# Addon-mapleCUx_HM-RFM69-RFM95-V12-001.net
KiCad netlist of a schematic drawn in EAGLE
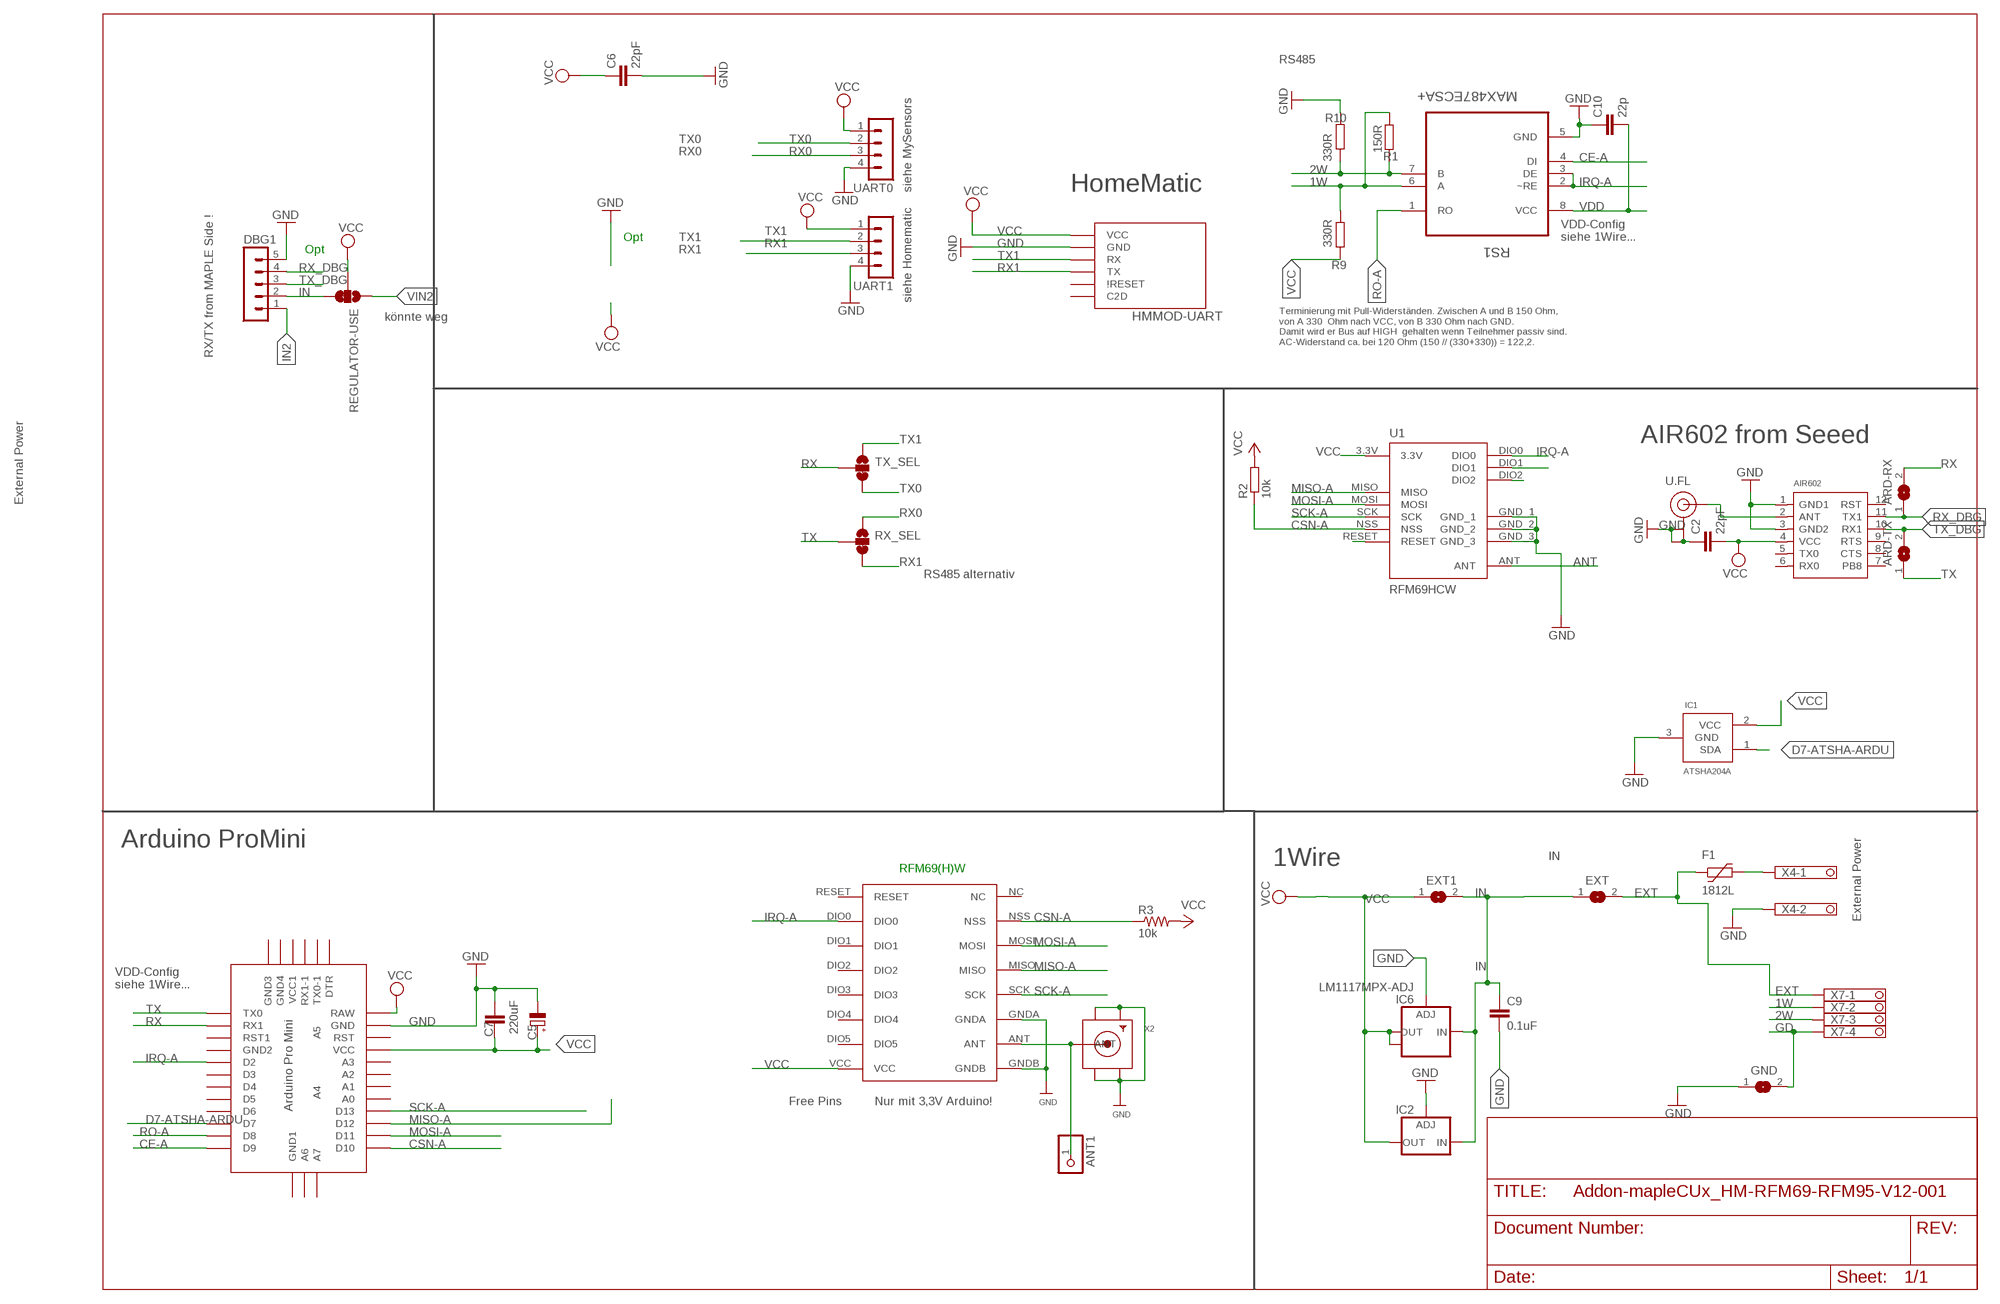
[diagram p0: schematic, sheet 1]

(export (version "E")
  (design (tool "Eeschema 10.0.6"))
  (components
    (comp (ref "AIR602")
      (value "AIR602")
      (footprint "eagle-import:MODULE12P-2.0-10X12MM")
      (libsource (lib "eagle-import") (part "AIR602"))
    )
    (comp (ref "ANT1")
      (value "PINHD-1X1")
      (footprint "eagle-import:1X01")
      (libsource (lib "eagle-import") (part "PINHD-1X1"))
    )
    (comp (ref "ARD-RX")
      (value "SJ")
      (footprint "eagle-import:SJ")
      (libsource (lib "eagle-import") (part "SJ"))
    )
    (comp (ref "ARD-TX")
      (value "SJ")
      (footprint "eagle-import:SJ")
      (libsource (lib "eagle-import") (part "SJ"))
    )
    (comp (ref "C2")
      (value "22pF")
      (footprint "eagle-import:C0805")
      (libsource (lib "eagle-import") (part "C-EUC0805"))
    )
    (comp (ref "C5")
      (value "220uF")
      (footprint "eagle-import:E5-8,5")
      (libsource (lib "eagle-import") (part "CPOL-EUE5-8.5"))
    )
    (comp (ref "C6")
      (value "22pF")
      (footprint "eagle-import:C0805")
      (libsource (lib "eagle-import") (part "C-EUC0805"))
    )
    (comp (ref "C7")
      (value "C-EUC1812")
      (footprint "eagle-import:C1812")
      (libsource (lib "eagle-import") (part "C-EUC1812"))
    )
    (comp (ref "C9")
      (value "0.1uF")
      (footprint "eagle-import:C1206")
      (libsource (lib "eagle-import") (part "C-EUC1206"))
    )
    (comp (ref "C10")
      (value "22p")
      (footprint "eagle-import:C0805")
      (libsource (lib "eagle-import") (part "C-EUC0805"))
    )
    (comp (ref "DBG1")
      (value "MA05-1")
      (footprint "eagle-import:MA05-1")
      (libsource (lib "eagle-import") (part "MA05-1"))
    )
    (comp (ref "EXT") (value "SJ") (footprint "eagle-import:SJ") (libsource (lib "eagle-import") (part "SJ")))
    (comp (ref "EXT1")
      (value "SJ")
      (footprint "eagle-import:SJ")
      (libsource (lib "eagle-import") (part "SJ"))
    )
    (comp (ref "F1")
      (value "1812L")
      (footprint "eagle-import:1812L")
      (libsource (lib "eagle-import") (part "1812L"))
    )
    (comp (ref "GND") (value "SJ") (footprint "eagle-import:SJ") (libsource (lib "eagle-import") (part "SJ")))
    (comp (ref "HMMOD-UART")
      (value "HM-MOD-UARTDIL")
      (footprint "eagle-import:HM-MOD-UART-DIL")
      (libsource (lib "eagle-import") (part "HM-MOD-UARTDIL"))
    )
    (comp (ref "IC1")
      (value "ATSHA204A")
      (footprint "eagle-import:SOT23")
      (libsource (lib "eagle-import") (part "ATSHA204A"))
    )
    (comp (ref "IC2")
      (value "LD117ADT50TR")
      (footprint "eagle-import:DPACK")
      (libsource (lib "eagle-import") (part "LD117A?DT50TR"))
    )
    (comp (ref "IC6")
      (value "LM1117MPX-ADJ")
      (footprint "eagle-import:SOT223")
      (libsource (lib "eagle-import") (part "LM1117MPX-ADJ"))
    )
    (comp (ref "R1")
      (value "150R")
      (footprint "eagle-import:R0805")
      (libsource (lib "eagle-import") (part "R-EU_R0805"))
    )
    (comp (ref "R2")
      (value "10k")
      (footprint "eagle-import:M0805")
      (libsource (lib "eagle-import") (part "R-EU_M0805"))
    )
    (comp (ref "R3")
      (value "10k")
      (footprint "eagle-import:0805")
      (libsource (lib "eagle-import") (part "RESISTOR0805-RES"))
    )
    (comp (ref "R9")
      (value "330R")
      (footprint "eagle-import:R0805")
      (libsource (lib "eagle-import") (part "R-EU_R0805"))
    )
    (comp (ref "R10")
      (value "330R")
      (footprint "eagle-import:R0805")
      (libsource (lib "eagle-import") (part "R-EU_R0805"))
    )
    (comp (ref "REGULATOR-USE")
      (value "JUMPER-SMT_3_1-NC_TRACE_SILK")
      (footprint "eagle-import:SMT-JUMPER_3_1-NC_TRACE_SILK")
      (libsource (lib "eagle-import") (part "JUMPER-SMT_3_1-NC_TRACE_SILK"))
    )
    (comp (ref "RFM69W")
      (value "RFM69HW")
      (footprint "eagle-import:RFM")
      (libsource (lib "eagle-import") (part "RFM69HW"))
    )
    (comp (ref "RS1")
      (value "MAX487ECSA+")
      (footprint "eagle-import:SOIC127P600X175-8N")
      (libsource (lib "eagle-import") (part "MAX487ECSA+"))
    )
    (comp (ref "RX_SEL")
      (value "JUMPER-SMT_3_1-NC_TRACE_SILK")
      (footprint "eagle-import:SMT-JUMPER_3_1-NC_TRACE_SILK")
      (libsource (lib "eagle-import") (part "JUMPER-SMT_3_1-NC_TRACE_SILK"))
    )
    (comp (ref "TX_SEL")
      (value "JUMPER-SMT_3_1-NC_TRACE_SILK")
      (footprint "eagle-import:SMT-JUMPER_3_1-NC_TRACE_SILK")
      (libsource (lib "eagle-import") (part "JUMPER-SMT_3_1-NC_TRACE_SILK"))
    )
    (comp (ref "U$2")
      (value "ABK-PRO-MINI")
      (footprint "eagle-import:ABK-PRO-MINI")
      (libsource (lib "eagle-import") (part "ABK-PRO-MINI"))
    )
    (comp (ref "U.FL")
      (value "U.FL")
      (footprint "eagle-import:U.FL")
      (libsource (lib "eagle-import") (part "U.FL"))
    )
    (comp (ref "U1")
      (value "RFM69HCW")
      (footprint "eagle-import:RFM69HCW-XXXS2")
      (libsource (lib "eagle-import") (part "RFM69HCW"))
    )
    (comp (ref "UART0")
      (value "MA04-1")
      (footprint "eagle-import:MA04-1")
      (libsource (lib "eagle-import") (part "MA04-1"))
    )
    (comp (ref "UART1")
      (value "MA04-1")
      (footprint "eagle-import:MA04-1")
      (libsource (lib "eagle-import") (part "MA04-1"))
    )
    (comp (ref "X2")
      (value "SMACONNECTOR_EDGE")
      (footprint "eagle-import:SMA_EDGELAUNCH")
      (libsource (lib "eagle-import") (part "SMACONNECTOR_EDGE"))
    )
    (comp (ref "X4")
      (value "1751248")
      (footprint "eagle-import:1751248")
      (libsource (lib "eagle-import") (part "1751248"))
    )
    (comp (ref "X7")
      (value "1751264")
      (footprint "eagle-import:1751264")
      (libsource (lib "eagle-import") (part "1751264"))
    )
  )
  (nets
    (net (code "1") (name "/1W") (class "Default")
      (node (ref "R1") (pin "1") (pinfunction "1_1") (pintype "passive"))
      (node (ref "R9") (pin "2") (pinfunction "2_2") (pintype "passive"))
      (node (ref "RS1") (pin "6") (pinfunction "A_6") (pintype "bidirectional"))
      (node (ref "X7") (pin "2") (pinfunction "K_2") (pintype "passive"))
    )
    (net (code "2") (name "/2W") (class "Default")
      (node (ref "R1") (pin "2") (pinfunction "2_2") (pintype "passive"))
      (node (ref "R10") (pin "1") (pinfunction "1_1") (pintype "passive"))
      (node (ref "RS1") (pin "7") (pinfunction "B_7") (pintype "bidirectional"))
      (node (ref "X7") (pin "3") (pinfunction "K_3") (pintype "passive"))
    )
    (net (code "3") (name "/ANT") (class "Default")
      (node (ref "ANT1") (pin "1") (pinfunction "1_1") (pintype "passive"))
      (node (ref "RFM69W") (pin "ANT") (pinfunction "ANT_ANT") (pintype "bidirectional"))
      (node (ref "U1") (pin "ANT") (pinfunction "ANT_ANT") (pintype "passive"))
      (node (ref "X2") (pin "P") (pinfunction "ANT_P") (pintype "bidirectional"))
    )
    (net (code "4") (name "/CE-A") (class "Default")
      (node (ref "RS1") (pin "4") (pinfunction "DI_4") (pintype "input"))
      (node (ref "U$2") (pin "D9") (pinfunction "D9_D9") (pintype "bidirectional"))
    )
    (net (code "5") (name "/CSN-A") (class "Default")
      (node (ref "R2") (pin "1") (pinfunction "1_1") (pintype "passive"))
      (node (ref "R3") (pin "1") (pinfunction "1_1") (pintype "passive"))
      (node (ref "RFM69W") (pin "NSS") (pinfunction "NSS_NSS") (pintype "bidirectional"))
      (node (ref "U$2") (pin "D10") (pinfunction "D10_D10") (pintype "bidirectional"))
      (node (ref "U1") (pin "NSS") (pinfunction "NSS_NSS") (pintype "input"))
    )
    (net (code "6") (name "/EXT") (class "Default")
      (node (ref "EXT") (pin "2") (pinfunction "2_2") (pintype "passive"))
      (node (ref "F1") (pin "P$1") (pinfunction "1_P$1") (pintype "passive"))
      (node (ref "X7") (pin "1") (pinfunction "K_1") (pintype "passive"))
    )
    (net (code "7") (name "/GD") (class "Default")
      (node (ref "GND") (pin "2") (pinfunction "2_2") (pintype "passive"))
      (node (ref "X7") (pin "4") (pinfunction "K_4") (pintype "passive"))
    )
    (net (code "8") (name "/IN") (class "Default")
      (node (ref "C9") (pin "1") (pinfunction "1_1") (pintype "passive"))
      (node (ref "DBG1") (pin "2") (pinfunction "2_2") (pintype "passive"))
      (node (ref "EXT") (pin "1") (pinfunction "1_1") (pintype "passive"))
      (node (ref "EXT1") (pin "2") (pinfunction "2_2") (pintype "passive"))
      (node (ref "IC2") (pin "3") (pinfunction "IN_3") (pintype "input"))
      (node (ref "IC6") (pin "3") (pinfunction "IN_3") (pintype "input"))
      (node (ref "REGULATOR-USE") (pin "3") (pinfunction "3_3") (pintype "passive"))
    )
    (net (code "9") (name "/IRQ-A") (class "Default")
      (node (ref "RFM69W") (pin "DIO0") (pinfunction "DIO0_DIO0") (pintype "bidirectional"))
      (node (ref "RS1") (pin "2") (pinfunction "~{RE}_2") (pintype "input"))
      (node (ref "RS1") (pin "3") (pinfunction "DE_3") (pintype "input"))
      (node (ref "U$2") (pin "D2") (pinfunction "D2_D2") (pintype "bidirectional"))
      (node (ref "U1") (pin "DIO0") (pinfunction "DIO0_DIO0") (pintype "bidirectional"))
    )
    (net (code "10") (name "/MISO-A") (class "Default")
      (node (ref "RFM69W") (pin "MISO") (pinfunction "MISO_MISO") (pintype "bidirectional"))
      (node (ref "U$2") (pin "D12") (pinfunction "D12_D12") (pintype "bidirectional"))
      (node (ref "U1") (pin "MISO") (pinfunction "MISO_MISO") (pintype "bidirectional"))
    )
    (net (code "11") (name "/MOSI-A") (class "Default")
      (node (ref "RFM69W") (pin "MOSI") (pinfunction "MOSI_MOSI") (pintype "bidirectional"))
      (node (ref "U$2") (pin "D11") (pinfunction "D11_D11") (pintype "bidirectional"))
      (node (ref "U1") (pin "MOSI") (pinfunction "MOSI_MOSI") (pintype "input"))
    )
    (net (code "12") (name "/RX") (class "Default")
      (node (ref "ARD-RX") (pin "2") (pinfunction "2_2") (pintype "passive"))
      (node (ref "TX_SEL") (pin "2") (pinfunction "2_2") (pintype "passive"))
      (node (ref "U$2") (pin "RX1") (pinfunction "RX1_RX1") (pintype "bidirectional"))
    )
    (net (code "13") (name "/RX0") (class "Default")
      (node (ref "RX_SEL") (pin "1") (pinfunction "1_1") (pintype "passive"))
      (node (ref "UART0") (pin "3") (pinfunction "3_3") (pintype "passive"))
    )
    (net (code "14") (name "/RX1") (class "Default")
      (node (ref "HMMOD-UART") (pin "5") (pinfunction "TX_5") (pintype "bidirectional"))
      (node (ref "RX_SEL") (pin "3") (pinfunction "3_3") (pintype "passive"))
      (node (ref "UART1") (pin "3") (pinfunction "3_3") (pintype "passive"))
    )
    (net (code "15") (name "/SCK-A") (class "Default")
      (node (ref "RFM69W") (pin "SCK") (pinfunction "SCK_SCK") (pintype "bidirectional"))
      (node (ref "U$2") (pin "D13") (pinfunction "D13_D13") (pintype "bidirectional"))
      (node (ref "U1") (pin "SCK") (pinfunction "SCK_SCK") (pintype "input"))
    )
    (net (code "16") (name "/TX") (class "Default")
      (node (ref "ARD-TX") (pin "1") (pinfunction "1_1") (pintype "passive"))
      (node (ref "RX_SEL") (pin "2") (pinfunction "2_2") (pintype "passive"))
      (node (ref "U$2") (pin "TX0") (pinfunction "TX0_TX0") (pintype "bidirectional"))
    )
    (net (code "17") (name "/TX0") (class "Default")
      (node (ref "TX_SEL") (pin "3") (pinfunction "3_3") (pintype "passive"))
      (node (ref "UART0") (pin "2") (pinfunction "2_2") (pintype "passive"))
    )
    (net (code "18") (name "/TX1") (class "Default")
      (node (ref "HMMOD-UART") (pin "6") (pinfunction "RX_6") (pintype "bidirectional"))
      (node (ref "TX_SEL") (pin "1") (pinfunction "1_1") (pintype "passive"))
      (node (ref "UART1") (pin "2") (pinfunction "2_2") (pintype "passive"))
    )
    (net (code "19") (name "/VDD") (class "Default")
      (node (ref "C10") (pin "2") (pinfunction "2_2") (pintype "passive"))
      (node (ref "RS1") (pin "8") (pinfunction "VCC_8") (pintype "power_in"))
    )
    (net (code "20") (name "D7-ATSHA-ARDU") (class "Default")
      (node (ref "IC1") (pin "1") (pinfunction "SDA_1") (pintype "bidirectional"))
      (node (ref "U$2") (pin "D7") (pinfunction "D7_D7") (pintype "bidirectional"))
    )
    (net (code "21") (name "GND") (class "Default")
      (node (ref "AIR602") (pin "1") (pinfunction "GND1_1") (pintype "bidirectional"))
      (node (ref "AIR602") (pin "3") (pinfunction "GND2_3") (pintype "bidirectional"))
      (node (ref "C10") (pin "1") (pinfunction "1_1") (pintype "passive"))
      (node (ref "C2") (pin "1") (pinfunction "1_1") (pintype "passive"))
      (node (ref "C5") (pin "-") (pinfunction "-_-") (pintype "passive"))
      (node (ref "C6") (pin "2") (pinfunction "2_2") (pintype "passive"))
      (node (ref "C7") (pin "1") (pinfunction "1_1") (pintype "passive"))
      (node (ref "C9") (pin "2") (pinfunction "2_2") (pintype "passive"))
      (node (ref "DBG1") (pin "5") (pinfunction "5_5") (pintype "passive"))
      (node (ref "GND") (pin "1") (pinfunction "1_1") (pintype "passive"))
      (node (ref "HMMOD-UART") (pin "2") (pinfunction "GND_2") (pintype "power_in"))
      (node (ref "IC1") (pin "3") (pinfunction "GND_3") (pintype "bidirectional"))
      (node (ref "IC2") (pin "1") (pinfunction "ADJ_1") (pintype "input"))
      (node (ref "IC6") (pin "1") (pinfunction "ADJ_1") (pintype "input"))
      (node (ref "R10") (pin "2") (pinfunction "2_2") (pintype "passive"))
      (node (ref "RFM69W") (pin "GNDA") (pinfunction "GNDA_GNDA") (pintype "bidirectional"))
      (node (ref "RFM69W") (pin "GNDB") (pinfunction "GNDB_GNDB") (pintype "bidirectional"))
      (node (ref "RS1") (pin "5") (pinfunction "GND_5") (pintype "passive"))
      (node (ref "U$2") (pin "GND") (pinfunction "GND_GND") (pintype "bidirectional"))
      (node (ref "U.FL") (pin "1") (pinfunction "GND_1") (pintype "bidirectional"))
      (node (ref "U.FL") (pin "2") (pinfunction "GND_2") (pintype "bidirectional"))
      (node (ref "U1") (pin "GND_1") (pinfunction "GND_1_GND_1") (pintype "power_in"))
      (node (ref "U1") (pin "GND_2") (pinfunction "GND_2_GND_2") (pintype "power_in"))
      (node (ref "U1") (pin "GND_3") (pinfunction "GND_3_GND_3") (pintype "power_in"))
      (node (ref "UART0") (pin "4") (pinfunction "4_4") (pintype "passive"))
      (node (ref "UART1") (pin "4") (pinfunction "4_4") (pintype "passive"))
      (node (ref "X2") (pin "GND@1") (pinfunction "GND4_GND@1") (pintype "power_in"))
      (node (ref "X2") (pin "GND@2") (pinfunction "GND3_GND@2") (pintype "power_in"))
      (node (ref "X2") (pin "GND@3") (pinfunction "GND2_GND@3") (pintype "power_in"))
      (node (ref "X2") (pin "GND@4") (pinfunction "GND1_GND@4") (pintype "power_in"))
      (node (ref "X4") (pin "2") (pinfunction "K_2") (pintype "passive"))
    )
    (net (code "22") (name "IN2") (class "Default")
      (node (ref "DBG1") (pin "1") (pinfunction "1_1") (pintype "passive"))
    )
    (net (code "23") (name "Net-(AIR602-ANT)") (class "Default")
      (node (ref "AIR602") (pin "2") (pinfunction "ANT_2") (pintype "bidirectional"))
      (node (ref "U.FL") (pin "FEED") (pinfunction "SIGNAL_FEED") (pintype "bidirectional"))
    )
    (net (code "24") (name "Net-(F1-2)") (class "Default")
      (node (ref "F1") (pin "P$2") (pinfunction "2_P$2") (pintype "passive"))
      (node (ref "X4") (pin "1") (pinfunction "K_1") (pintype "passive"))
    )
    (net (code "25") (name "RO-A") (class "Default")
      (node (ref "RS1") (pin "1") (pinfunction "RO_1") (pintype "output"))
      (node (ref "U$2") (pin "D8") (pinfunction "D8_D8") (pintype "bidirectional"))
    )
    (net (code "26") (name "RX_DBG") (class "Default")
      (node (ref "AIR602") (pin "11") (pinfunction "TX1_11") (pintype "bidirectional"))
      (node (ref "ARD-RX") (pin "1") (pinfunction "1_1") (pintype "passive"))
      (node (ref "DBG1") (pin "4") (pinfunction "4_4") (pintype "passive"))
    )
    (net (code "27") (name "TX_DBG") (class "Default")
      (node (ref "AIR602") (pin "10") (pinfunction "RX1_10") (pintype "bidirectional"))
      (node (ref "ARD-TX") (pin "2") (pinfunction "2_2") (pintype "passive"))
      (node (ref "DBG1") (pin "3") (pinfunction "3_3") (pintype "passive"))
    )
    (net (code "28") (name "VCC") (class "Default")
      (node (ref "AIR602") (pin "4") (pinfunction "VCC_4") (pintype "bidirectional"))
      (node (ref "C2") (pin "2") (pinfunction "2_2") (pintype "passive"))
      (node (ref "C5") (pin "+") (pinfunction "+_+") (pintype "passive"))
      (node (ref "C6") (pin "1") (pinfunction "1_1") (pintype "passive"))
      (node (ref "C7") (pin "2") (pinfunction "2_2") (pintype "passive"))
      (node (ref "EXT1") (pin "1") (pinfunction "1_1") (pintype "passive"))
      (node (ref "HMMOD-UART") (pin "1") (pinfunction "VCC_1") (pintype "power_in"))
      (node (ref "IC1") (pin "2") (pinfunction "VCC_2") (pintype "bidirectional"))
      (node (ref "IC2") (pin "4") (pinfunction "OUT_4") (pintype "passive"))
      (node (ref "IC6") (pin "2") (pinfunction "OUT_2") (pintype "passive"))
      (node (ref "IC6") (pin "TAB") (pinfunction "OUT1_TAB") (pintype "passive"))
      (node (ref "R2") (pin "2") (pinfunction "2_2") (pintype "passive"))
      (node (ref "R3") (pin "2") (pinfunction "2_2") (pintype "passive"))
      (node (ref "R9") (pin "1") (pinfunction "1_1") (pintype "passive"))
      (node (ref "REGULATOR-USE") (pin "2") (pinfunction "2_2") (pintype "passive"))
      (node (ref "RFM69W") (pin "VCC") (pinfunction "VCC_VCC") (pintype "bidirectional"))
      (node (ref "U$2") (pin "RAW") (pinfunction "RAW_RAW") (pintype "bidirectional"))
      (node (ref "U$2") (pin "VCC") (pinfunction "VCC_VCC") (pintype "bidirectional"))
      (node (ref "U1") (pin "3.3V") (pinfunction "3.3V_3.3V") (pintype "power_in"))
      (node (ref "UART0") (pin "1") (pinfunction "1_1") (pintype "passive"))
      (node (ref "UART1") (pin "1") (pinfunction "1_1") (pintype "passive"))
    )
    (net (code "29") (name "VIN2") (class "Default")
      (node (ref "REGULATOR-USE") (pin "1") (pinfunction "1_1") (pintype "passive"))
    )
    (net (code "30") (name "unconnected-(AIR602-CTS-Pad8)") (class "Default")
      (node (ref "AIR602") (pin "8") (pinfunction "CTS_8") (pintype "bidirectional"))
    )
    (net (code "31") (name "unconnected-(AIR602-PB8-Pad7)") (class "Default")
      (node (ref "AIR602") (pin "7") (pinfunction "PB8_7") (pintype "bidirectional"))
    )
    (net (code "32") (name "unconnected-(AIR602-RST-Pad12)") (class "Default")
      (node (ref "AIR602") (pin "12") (pinfunction "RST_12") (pintype "bidirectional"))
    )
    (net (code "33") (name "unconnected-(AIR602-RTS-Pad9)") (class "Default")
      (node (ref "AIR602") (pin "9") (pinfunction "RTS_9") (pintype "bidirectional"))
    )
    (net (code "34") (name "unconnected-(AIR602-RX0-Pad6)") (class "Default")
      (node (ref "AIR602") (pin "6") (pinfunction "RX0_6") (pintype "bidirectional"))
    )
    (net (code "35") (name "unconnected-(AIR602-TX0-Pad5)") (class "Default")
      (node (ref "AIR602") (pin "5") (pinfunction "TX0_5") (pintype "bidirectional"))
    )
    (net (code "36") (name "unconnected-(HMMOD-UART-C2D-Pad3)") (class "Default")
      (node (ref "HMMOD-UART") (pin "3") (pinfunction "C2D_3") (pintype "bidirectional"))
    )
    (net (code "37") (name "unconnected-(HMMOD-UART-\\~{RESET}-Pad4)") (class "Default")
      (node (ref "HMMOD-UART") (pin "4") (pinfunction "\\~{RESET}_4") (pintype "bidirectional"))
    )
    (net (code "38") (name "unconnected-(RFM69W-PadDIO1)") (class "Default")
      (node (ref "RFM69W") (pin "DIO1") (pinfunction "DIO1_DIO1") (pintype "bidirectional"))
    )
    (net (code "39") (name "unconnected-(RFM69W-PadDIO2)") (class "Default")
      (node (ref "RFM69W") (pin "DIO2") (pinfunction "DIO2_DIO2") (pintype "bidirectional"))
    )
    (net (code "40") (name "unconnected-(RFM69W-PadDIO3)") (class "Default")
      (node (ref "RFM69W") (pin "DIO3") (pinfunction "DIO3_DIO3") (pintype "bidirectional"))
    )
    (net (code "41") (name "unconnected-(RFM69W-PadDIO4)") (class "Default")
      (node (ref "RFM69W") (pin "DIO4") (pinfunction "DIO4_DIO4") (pintype "bidirectional"))
    )
    (net (code "42") (name "unconnected-(RFM69W-PadDIO5)") (class "Default")
      (node (ref "RFM69W") (pin "DIO5") (pinfunction "DIO5_DIO5") (pintype "bidirectional"))
    )
    (net (code "43") (name "unconnected-(RFM69W-PadNC)") (class "Default")
      (node (ref "RFM69W") (pin "NC") (pinfunction "NC_NC") (pintype "bidirectional"))
    )
    (net (code "44") (name "unconnected-(RFM69W-PadRESET)") (class "Default")
      (node (ref "RFM69W") (pin "RESET") (pinfunction "RESET_RESET") (pintype "bidirectional"))
    )
    (net (code "45") (name "unconnected-(U$2-GND1-PadGND4)") (class "Default")
      (node (ref "U$2") (pin "GND4") (pinfunction "GND1_GND4") (pintype "bidirectional"))
    )
    (net (code "46") (name "unconnected-(U$2-GND2-PadGND1)") (class "Default")
      (node (ref "U$2") (pin "GND1") (pinfunction "GND2_GND1") (pintype "bidirectional"))
    )
    (net (code "47") (name "unconnected-(U$2-GND3-PadGND2)") (class "Default")
      (node (ref "U$2") (pin "GND2") (pinfunction "GND3_GND2") (pintype "bidirectional"))
    )
    (net (code "48") (name "unconnected-(U$2-GND4-PadGND3)") (class "Default")
      (node (ref "U$2") (pin "GND3") (pinfunction "GND4_GND3") (pintype "bidirectional"))
    )
    (net (code "49") (name "unconnected-(U$2-PadA0)") (class "Default")
      (node (ref "U$2") (pin "A0") (pinfunction "A0_A0") (pintype "bidirectional"))
    )
    (net (code "50") (name "unconnected-(U$2-PadA1)") (class "Default")
      (node (ref "U$2") (pin "A1") (pinfunction "A1_A1") (pintype "bidirectional"))
    )
    (net (code "51") (name "unconnected-(U$2-PadA2)") (class "Default")
      (node (ref "U$2") (pin "A2") (pinfunction "A2_A2") (pintype "bidirectional"))
    )
    (net (code "52") (name "unconnected-(U$2-PadA3)") (class "Default")
      (node (ref "U$2") (pin "A3") (pinfunction "A3_A3") (pintype "bidirectional"))
    )
    (net (code "53") (name "unconnected-(U$2-PadA4)") (class "Default")
      (node (ref "U$2") (pin "A4") (pinfunction "A4_A4") (pintype "bidirectional"))
    )
    (net (code "54") (name "unconnected-(U$2-PadA5)") (class "Default")
      (node (ref "U$2") (pin "A5") (pinfunction "A5_A5") (pintype "bidirectional"))
    )
    (net (code "55") (name "unconnected-(U$2-PadA6)") (class "Default")
      (node (ref "U$2") (pin "A6") (pinfunction "A6_A6") (pintype "bidirectional"))
    )
    (net (code "56") (name "unconnected-(U$2-PadA7)") (class "Default")
      (node (ref "U$2") (pin "A7") (pinfunction "A7_A7") (pintype "bidirectional"))
    )
    (net (code "57") (name "unconnected-(U$2-PadD3)") (class "Default")
      (node (ref "U$2") (pin "D3") (pinfunction "D3_D3") (pintype "bidirectional"))
    )
    (net (code "58") (name "unconnected-(U$2-PadD4)") (class "Default")
      (node (ref "U$2") (pin "D4") (pinfunction "D4_D4") (pintype "bidirectional"))
    )
    (net (code "59") (name "unconnected-(U$2-PadD5)") (class "Default")
      (node (ref "U$2") (pin "D5") (pinfunction "D5_D5") (pintype "bidirectional"))
    )
    (net (code "60") (name "unconnected-(U$2-PadD6)") (class "Default")
      (node (ref "U$2") (pin "D6") (pinfunction "D6_D6") (pintype "bidirectional"))
    )
    (net (code "61") (name "unconnected-(U$2-PadDTR)") (class "Default")
      (node (ref "U$2") (pin "DTR") (pinfunction "DTR_DTR") (pintype "bidirectional"))
    )
    (net (code "62") (name "unconnected-(U$2-PadRST)") (class "Default")
      (node (ref "U$2") (pin "RST") (pinfunction "RST_RST") (pintype "bidirectional"))
    )
    (net (code "63") (name "unconnected-(U$2-PadRST1)") (class "Default")
      (node (ref "U$2") (pin "RST1") (pinfunction "RST1_RST1") (pintype "bidirectional"))
    )
    (net (code "64") (name "unconnected-(U$2-PadRX1-1)") (class "Default")
      (node (ref "U$2") (pin "RX1-1") (pinfunction "RX1-1_RX1-1") (pintype "bidirectional"))
    )
    (net (code "65") (name "unconnected-(U$2-PadTX0-1)") (class "Default")
      (node (ref "U$2") (pin "TX0-1") (pinfunction "TX0-1_TX0-1") (pintype "bidirectional"))
    )
    (net (code "66") (name "unconnected-(U$2-PadVCC1)") (class "Default")
      (node (ref "U$2") (pin "VCC1") (pinfunction "VCC1_VCC1") (pintype "bidirectional"))
    )
    (net (code "67") (name "unconnected-(U1-PadDIO1)") (class "Default")
      (node (ref "U1") (pin "DIO1") (pinfunction "DIO1_DIO1") (pintype "bidirectional"))
    )
    (net (code "68") (name "unconnected-(U1-PadDIO2)") (class "Default")
      (node (ref "U1") (pin "DIO2") (pinfunction "DIO2_DIO2") (pintype "bidirectional"))
    )
    (net (code "69") (name "unconnected-(U1-PadRESET)") (class "Default")
      (node (ref "U1") (pin "RESET") (pinfunction "RESET_RESET") (pintype "input"))
    )
  )
)
